# Brake_Schematic.net
KiCad netlist of a schematic drawn in EasyEDA
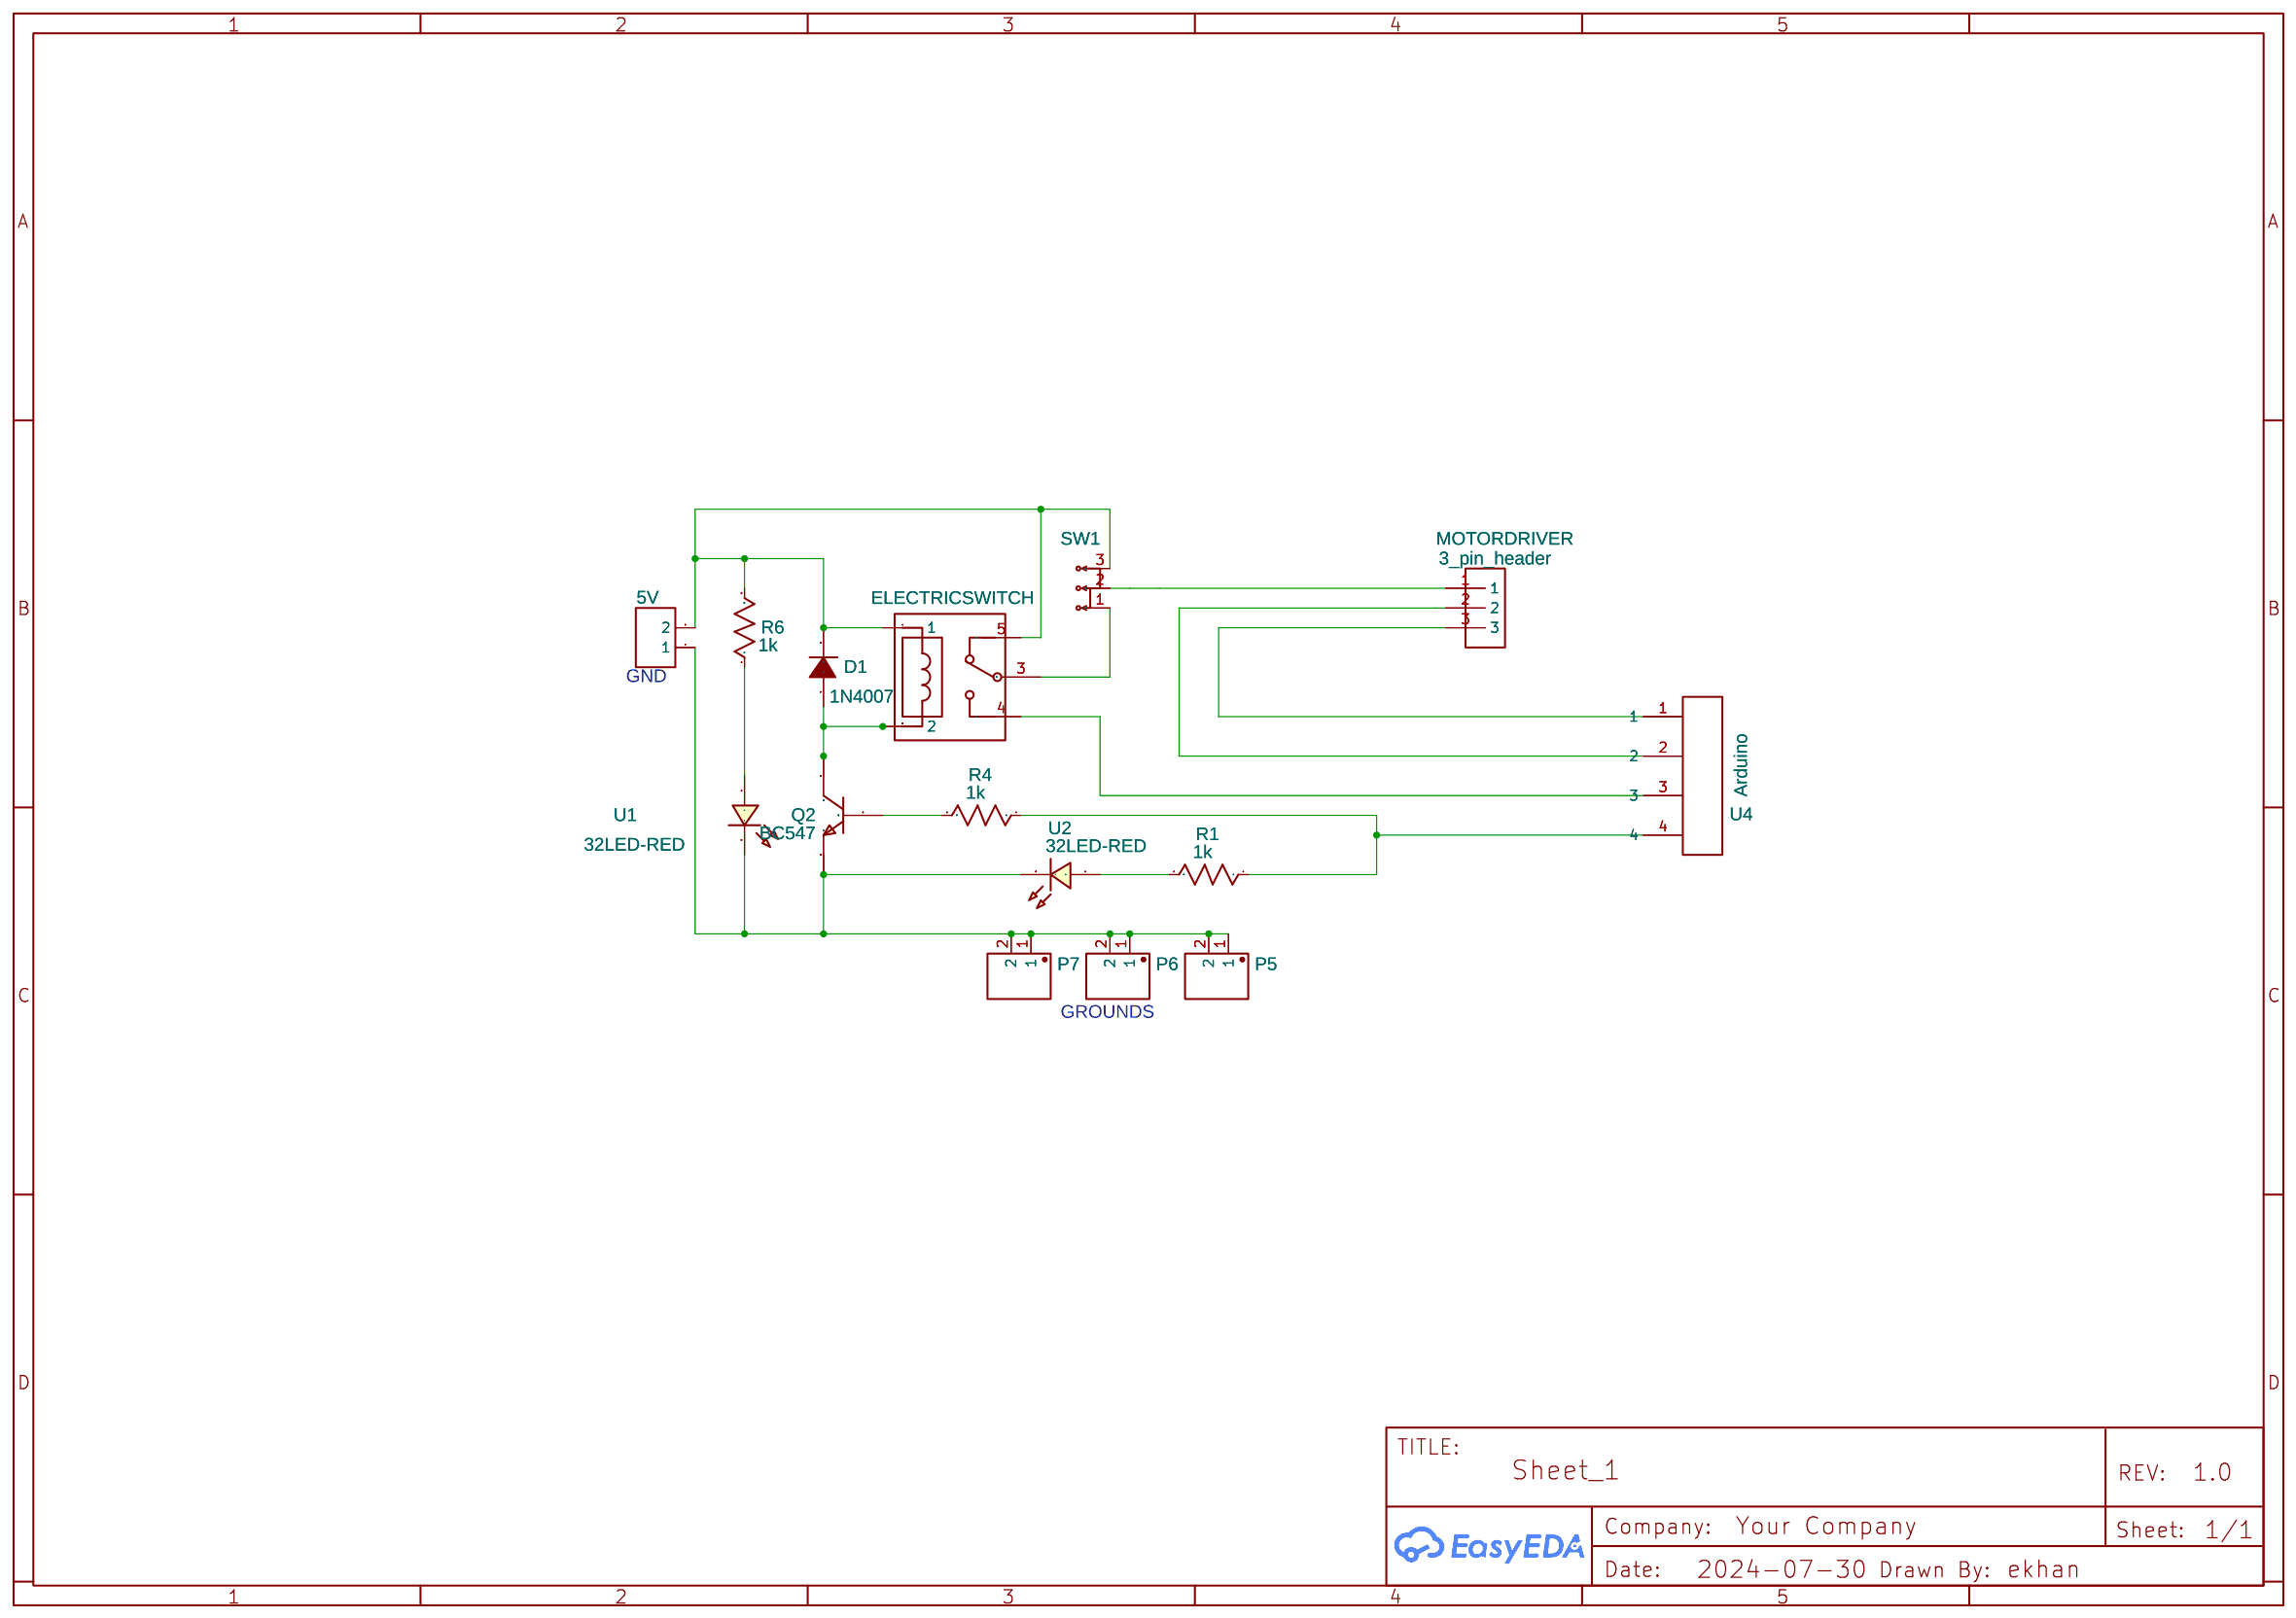
[diagram p0: schematic sheet]

(export (version "E")
  (design (tool "Eeschema 10.0.6"))
  (components
    (comp (ref "5V") (value "200mils 2pin Header") (libsource (lib "") (part "200mils 2pin Header")))
    (comp (ref "D1")
      (value "1N4007")
      (fields (field (name "Manufacturer") "ST(先科)"))
      (libsource (lib "") (part "1N4007"))
    )
    (comp (ref "ELECTRICSWITCH") (value "HRS4H-S-5v") (libsource (lib "") (part "HRS4H-S-5v")))
    (comp (ref "MOTORDRIVER") (value "3_pin_header") (libsource (lib "") (part "3_pin_header")))
    (comp (ref "P5")
      (value "TERMINAL2P_H")
      (fields (field (name "Manufacturer Part") "CH5.08-2A") (field (name "Manufacturer") "BOOMELE"))
      (libsource (lib "") (part "TERMINAL2P_H"))
    )
    (comp (ref "P6")
      (value "TERMINAL2P_H")
      (fields (field (name "Manufacturer Part") "CH5.08-2A") (field (name "Manufacturer") "BOOMELE"))
      (libsource (lib "") (part "TERMINAL2P_H"))
    )
    (comp (ref "P7")
      (value "TERMINAL2P_H")
      (fields (field (name "Manufacturer Part") "CH5.08-2A") (field (name "Manufacturer") "BOOMELE"))
      (libsource (lib "") (part "TERMINAL2P_H"))
    )
    (comp (ref "Q2") (value "BC547") (libsource (lib "") (part "BC547")))
    (comp (ref "R1") (value "1k") (libsource (lib "") (part "R_AXIAL-0.3_US_1")))
    (comp (ref "R4") (value "1k") (libsource (lib "") (part "R_AXIAL-0.3_US_1")))
    (comp (ref "R6") (value "1k") (libsource (lib "") (part "R_AXIAL-0.3_US")))
    (comp (ref "SW1") (value "SS12D00G3") (libsource (lib "") (part "SS12D00G3")))
    (comp (ref "U1")
      (value "32LED-RED")
      (fields (field (name "Manufacturer") "Grayhill"))
      (libsource (lib "") (part "32LED-RED"))
    )
    (comp (ref "U2")
      (value "32LED-RED")
      (fields (field (name "Manufacturer") "Grayhill"))
      (libsource (lib "") (part "32LED-RED_1"))
    )
    (comp (ref "U4") (value "Arduino") (libsource (lib "") (part "200mils_4Pin_Header")))
  )
  (nets
    (net (code "1") (name "Net-(D1-A)") (class "Default")
      (node (ref "D1") (pin "2") (pinfunction "A_2") (pintype "unspecified"))
      (node (ref "ELECTRICSWITCH") (pin "2") (pinfunction "2_2") (pintype "unspecified"))
      (node (ref "Q2") (pin "1") (pinfunction "C_1") (pintype "unspecified"))
    )
    (net (code "2") (name "Net-(D1-K)") (class "Default")
      (node (ref "5V") (pin "2") (pinfunction "2_2") (pintype "unspecified"))
      (node (ref "D1") (pin "1") (pinfunction "K_1") (pintype "unspecified"))
      (node (ref "ELECTRICSWITCH") (pin "1") (pinfunction "1_1") (pintype "unspecified"))
      (node (ref "ELECTRICSWITCH") (pin "5") (pinfunction "5_5") (pintype "unspecified"))
      (node (ref "R6") (pin "2") (pinfunction "2_2") (pintype "unspecified"))
      (node (ref "SW1") (pin "3") (pinfunction "3_3") (pintype "unspecified"))
    )
    (net (code "3") (name "Net-(ELECTRICSWITCH-Pad3)") (class "Default")
      (node (ref "ELECTRICSWITCH") (pin "3") (pinfunction "3_3") (pintype "unspecified"))
      (node (ref "SW1") (pin "1") (pinfunction "1_1") (pintype "unspecified"))
    )
    (net (code "4") (name "Net-(ELECTRICSWITCH-Pad4)") (class "Default")
      (node (ref "ELECTRICSWITCH") (pin "4") (pinfunction "4_4") (pintype "unspecified"))
      (node (ref "U4") (pin "3") (pinfunction "3_3") (pintype "unspecified"))
    )
    (net (code "5") (name "Net-(MOTORDRIVER-Pad1)") (class "Default")
      (node (ref "MOTORDRIVER") (pin "1") (pinfunction "1_1") (pintype "unspecified"))
      (node (ref "SW1") (pin "2") (pinfunction "2_2") (pintype "unspecified"))
    )
    (net (code "6") (name "Net-(MOTORDRIVER-Pad2)") (class "Default")
      (node (ref "MOTORDRIVER") (pin "2") (pinfunction "2_2") (pintype "unspecified"))
      (node (ref "U4") (pin "2") (pinfunction "2_2") (pintype "unspecified"))
    )
    (net (code "7") (name "Net-(MOTORDRIVER-Pad3)") (class "Default")
      (node (ref "MOTORDRIVER") (pin "3") (pinfunction "3_3") (pintype "unspecified"))
      (node (ref "U4") (pin "1") (pinfunction "1_1") (pintype "unspecified"))
    )
    (net (code "8") (name "Net-(Q2-B)") (class "Default")
      (node (ref "Q2") (pin "2") (pinfunction "B_2") (pintype "unspecified"))
      (node (ref "R4") (pin "2") (pinfunction "2_2") (pintype "unspecified"))
    )
    (net (code "9") (name "Net-(Q2-E)") (class "Default")
      (node (ref "5V") (pin "1") (pinfunction "1_1") (pintype "unspecified"))
      (node (ref "P5") (pin "1") (pinfunction "1_1") (pintype "unspecified"))
      (node (ref "P5") (pin "2") (pinfunction "2_2") (pintype "unspecified"))
      (node (ref "P6") (pin "1") (pinfunction "1_1") (pintype "unspecified"))
      (node (ref "P6") (pin "2") (pinfunction "2_2") (pintype "unspecified"))
      (node (ref "P7") (pin "1") (pinfunction "1_1") (pintype "unspecified"))
      (node (ref "P7") (pin "2") (pinfunction "2_2") (pintype "unspecified"))
      (node (ref "Q2") (pin "3") (pinfunction "E_3") (pintype "unspecified"))
      (node (ref "U1") (pin "2") (pinfunction "-_2") (pintype "unspecified"))
      (node (ref "U2") (pin "2") (pinfunction "-_2") (pintype "unspecified"))
    )
    (net (code "10") (name "Net-(R1-Pad1)") (class "Default")
      (node (ref "R1") (pin "1") (pinfunction "1_1") (pintype "unspecified"))
      (node (ref "R4") (pin "1") (pinfunction "1_1") (pintype "unspecified"))
      (node (ref "U4") (pin "4") (pinfunction "4_4") (pintype "unspecified"))
    )
    (net (code "11") (name "Net-(U1-+)") (class "Default")
      (node (ref "R6") (pin "1") (pinfunction "1_1") (pintype "unspecified"))
      (node (ref "U1") (pin "1") (pinfunction "+_1") (pintype "unspecified"))
    )
    (net (code "12") (name "Net-(U2-+)") (class "Default")
      (node (ref "R1") (pin "2") (pinfunction "2_2") (pintype "unspecified"))
      (node (ref "U2") (pin "1") (pinfunction "+_1") (pintype "unspecified"))
    )
  )
)
